# Atom_Multiout_Addon_Comp-9p.net
KiCad netlist of a schematic drawn in EAGLE
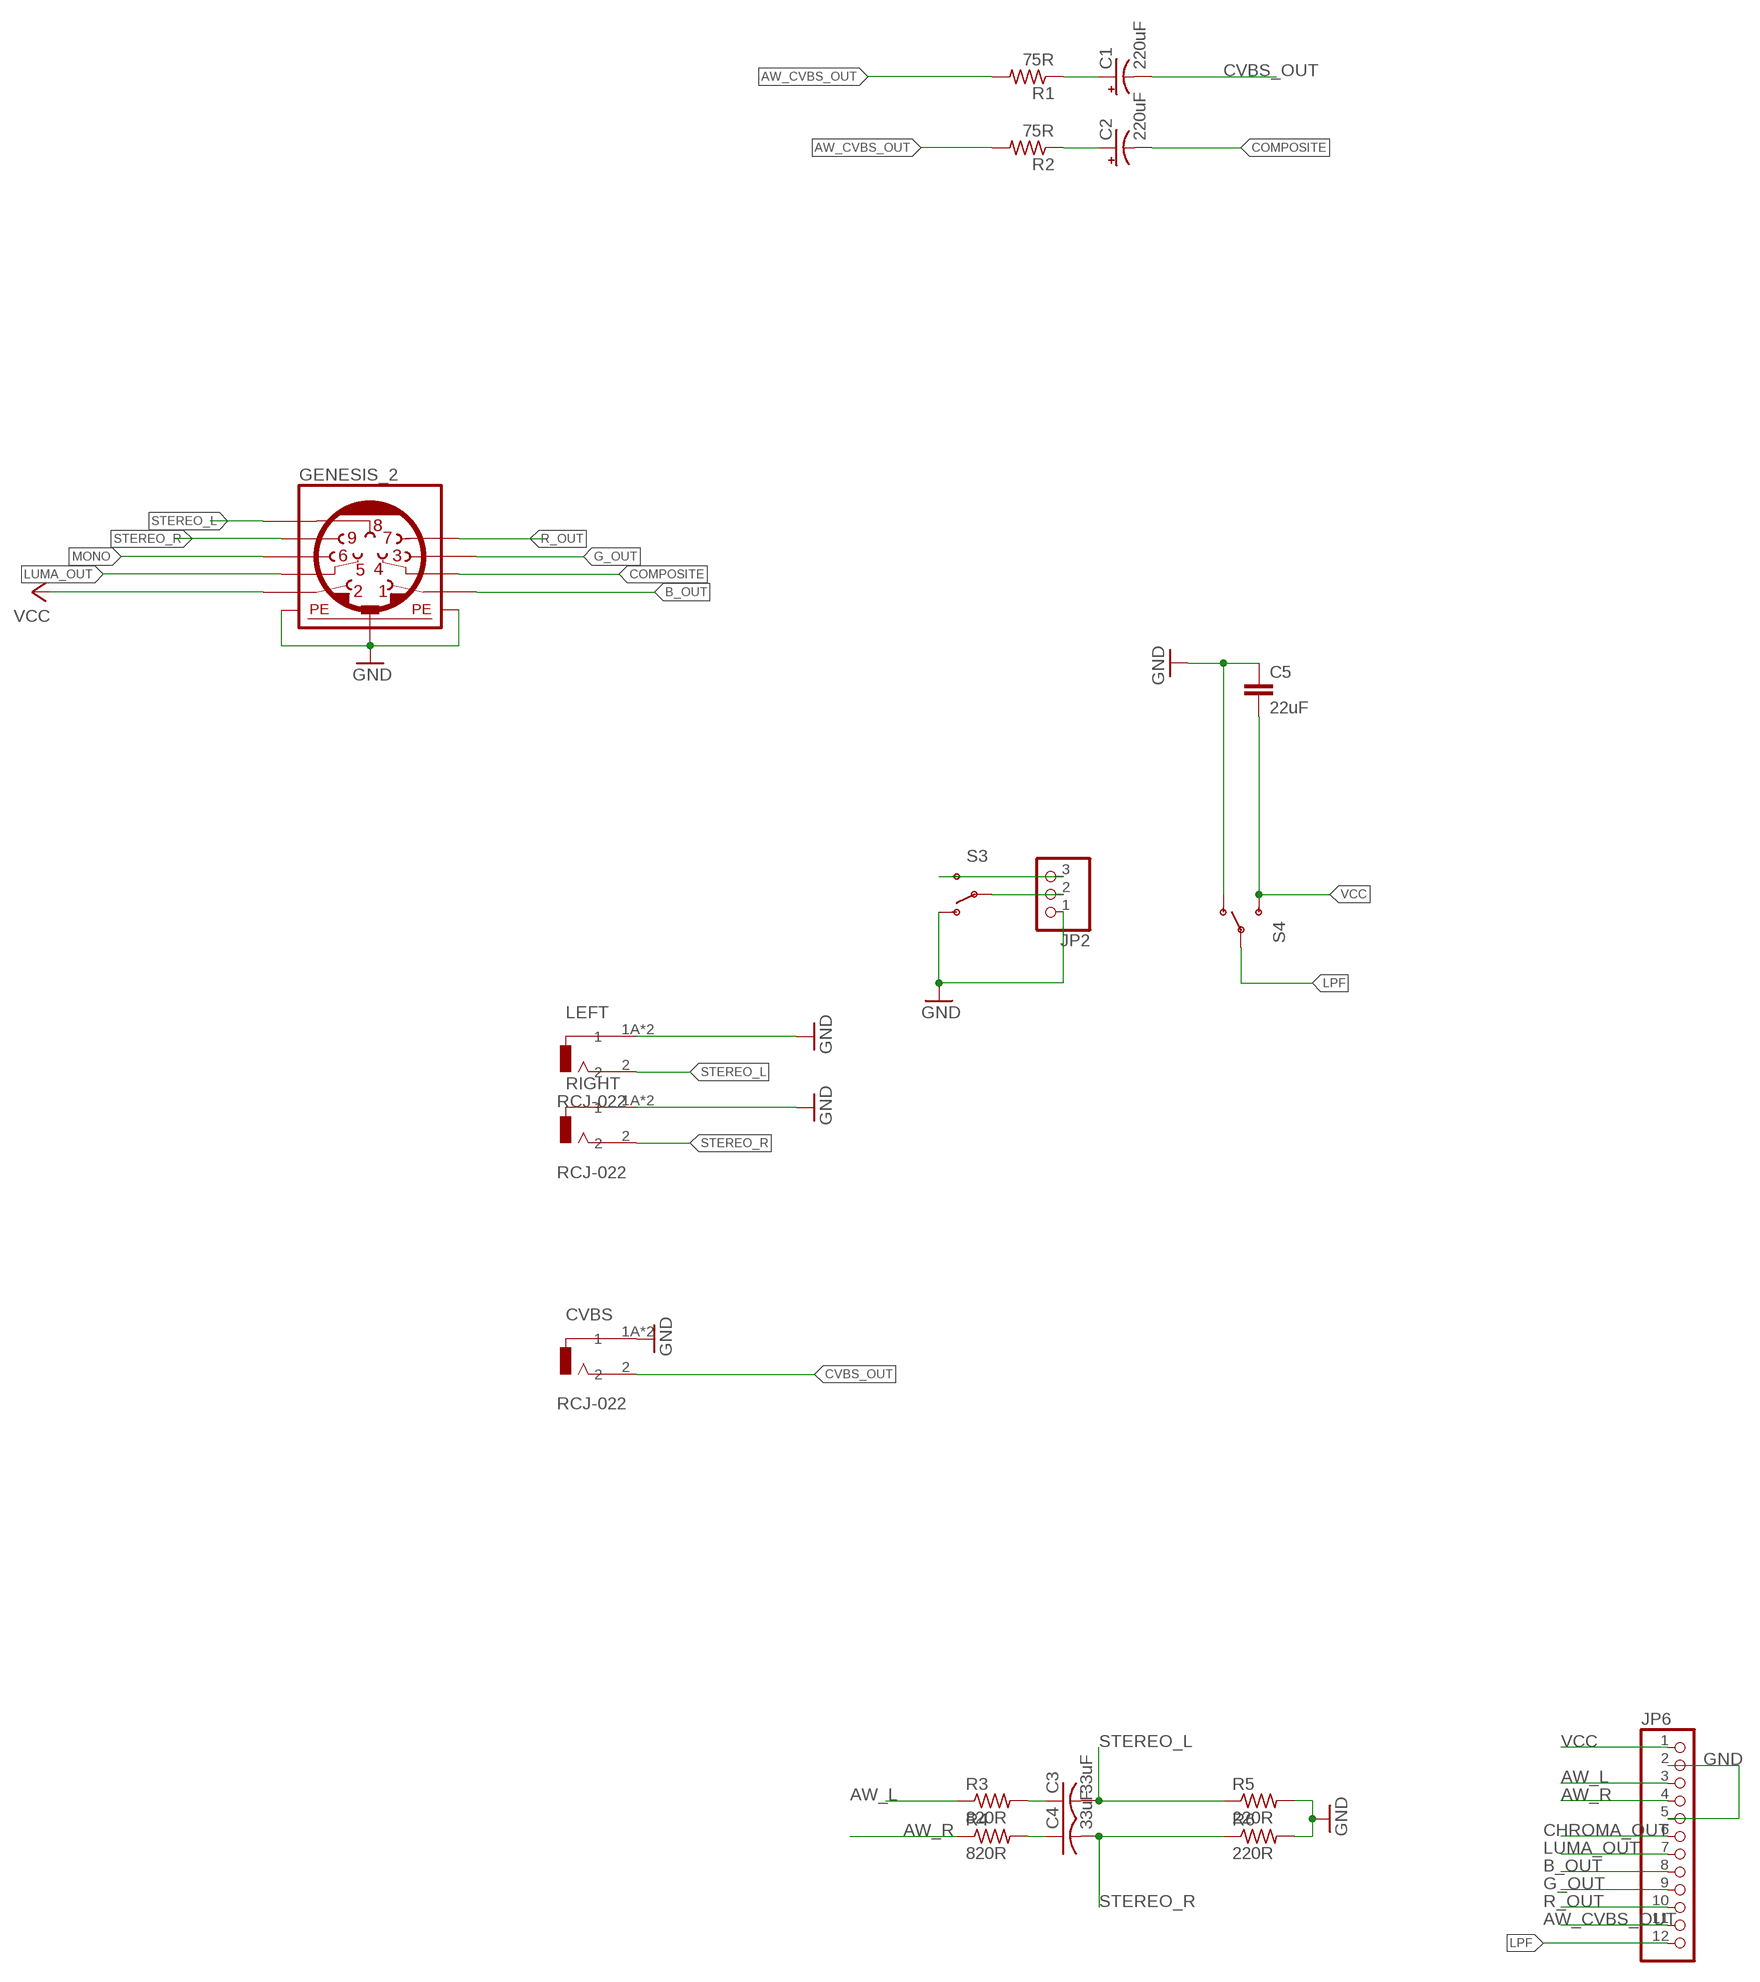
[diagram p0: schematic, sheet 1]

(export (version "E")
  (design (tool "Eeschema 10.0.6"))
  (components
    (comp (ref "C1")
      (value "220uF")
      (footprint "eagle-import:D_7343-31W")
      (libsource (lib "eagle-import") (part "CPOL-USD/7343-31W"))
    )
    (comp (ref "C2")
      (value "220uF")
      (footprint "eagle-import:D_7343-31W")
      (libsource (lib "eagle-import") (part "CPOL-USD/7343-31W"))
    )
    (comp (ref "C3")
      (value "33uF")
      (footprint "eagle-import:C1206K")
      (libsource (lib "eagle-import") (part "C-USC1206K"))
    )
    (comp (ref "C4")
      (value "33uF")
      (footprint "eagle-import:C1206K")
      (libsource (lib "eagle-import") (part "C-USC1206K"))
    )
    (comp (ref "C5")
      (value "22uF")
      (footprint "eagle-import:C0603")
      (libsource (lib "eagle-import") (part "C-EUC0603"))
    )
    (comp (ref "CVBS")
      (value "RCJ-022")
      (footprint "eagle-import:CUI_RCJ-022")
      (fields (field (name "MF") "CUI Devices"))
      (libsource (lib "eagle-import") (part "RCJ-022"))
    )
    (comp (ref "GENESIS_2")
      (value "MINI_DIN_9")
      (footprint "eagle-import:M_DIN9")
      (libsource (lib "eagle-import") (part "MINI_DIN_9"))
    )
    (comp (ref "JP2")
      (value "PINHD-1X03_2.54-S")
      (footprint "eagle-import:1X03-S")
      (libsource (lib "eagle-import") (part "PINHD-1X03_2.54-S"))
    )
    (comp (ref "JP6")
      (value "PINHD-1X12_2.54-S")
      (footprint "eagle-import:1X12-S")
      (libsource (lib "eagle-import") (part "PINHD-1X12_2.54-S"))
    )
    (comp (ref "LEFT")
      (value "RCJ-022")
      (footprint "eagle-import:CUI_RCJ-022")
      (fields (field (name "MF") "CUI Devices"))
      (libsource (lib "eagle-import") (part "RCJ-022"))
    )
    (comp (ref "R1")
      (value "75R")
      (footprint "eagle-import:R1206")
      (libsource (lib "eagle-import") (part "resistor_348_R-US_R1206"))
    )
    (comp (ref "R2")
      (value "75R")
      (footprint "eagle-import:R1206")
      (libsource (lib "eagle-import") (part "R-US_R1206"))
    )
    (comp (ref "R3")
      (value "820R")
      (footprint "eagle-import:R1206")
      (libsource (lib "eagle-import") (part "resistor_348_R-US_R1206"))
    )
    (comp (ref "R4")
      (value "820R")
      (footprint "eagle-import:R1206")
      (libsource (lib "eagle-import") (part "resistor_348_R-US_R1206"))
    )
    (comp (ref "R5")
      (value "220R")
      (footprint "eagle-import:R1206")
      (libsource (lib "eagle-import") (part "resistor_348_R-US_R1206"))
    )
    (comp (ref "R6")
      (value "220R")
      (footprint "eagle-import:R1206")
      (libsource (lib "eagle-import") (part "resistor_348_R-US_R1206"))
    )
    (comp (ref "RIGHT")
      (value "RCJ-022")
      (footprint "eagle-import:CUI_RCJ-022")
      (fields (field (name "MF") "CUI Devices"))
      (libsource (lib "eagle-import") (part "RCJ-022"))
    )
    (comp (ref "S3")
      (value "SWITCH-SPDT-SMD-A")
      (footprint "eagle-import:SWITCH-SPST-SMD-A")
      (libsource (lib "eagle-import") (part "SWITCH-SPDT-SMD-A"))
    )
    (comp (ref "S4")
      (value "SWITCH-SPDT-SMD-A")
      (footprint "eagle-import:SWITCH-SPST-SMD-A")
      (libsource (lib "eagle-import") (part "SWITCH-SPDT-SMD-A"))
    )
  )
  (nets
    (net (code "1") (name "/AW_L") (class "Default")
      (node (ref "JP6") (pin "3") (pinfunction "3_3") (pintype "passive"))
      (node (ref "R3") (pin "1") (pinfunction "1_1") (pintype "passive"))
    )
    (net (code "2") (name "/AW_R") (class "Default")
      (node (ref "JP6") (pin "4") (pinfunction "4_4") (pintype "passive"))
      (node (ref "R4") (pin "1") (pinfunction "1_1") (pintype "passive"))
    )
    (net (code "3") (name "/CHROMA_OUT") (class "Default")
      (node (ref "JP6") (pin "6") (pinfunction "6_6") (pintype "passive"))
    )
    (net (code "4") (name "AW_CVBS_OUT") (class "Default")
      (node (ref "JP6") (pin "11") (pinfunction "11_11") (pintype "passive"))
      (node (ref "R1") (pin "2") (pinfunction "2_2") (pintype "passive"))
      (node (ref "R2") (pin "2") (pinfunction "2_2") (pintype "passive"))
    )
    (net (code "5") (name "B_OUT") (class "Default")
      (node (ref "GENESIS_2") (pin "1") (pinfunction "1_1") (pintype "passive"))
      (node (ref "JP6") (pin "8") (pinfunction "8_8") (pintype "passive"))
    )
    (net (code "6") (name "COMPOSITE") (class "Default")
      (node (ref "C2") (pin "-") (pinfunction "-_-") (pintype "passive"))
      (node (ref "GENESIS_2") (pin "4") (pinfunction "4_4") (pintype "passive"))
    )
    (net (code "7") (name "CVBS_OUT") (class "Default")
      (node (ref "C1") (pin "-") (pinfunction "-_-") (pintype "passive"))
      (node (ref "CVBS") (pin "2") (pinfunction "2_2") (pintype "passive"))
    )
    (net (code "8") (name "GND") (class "Default")
      (node (ref "C5") (pin "1") (pinfunction "1_1") (pintype "passive"))
      (node (ref "CVBS") (pin "1A") (pinfunction "1_1A") (pintype "passive"))
      (node (ref "CVBS") (pin "1B") (pinfunction "1_1B") (pintype "passive"))
      (node (ref "GENESIS_2") (pin "SH1") (pinfunction "PE1_SH1") (pintype "power_in"))
      (node (ref "GENESIS_2") (pin "SH2") (pinfunction "PE2_SH2") (pintype "power_in"))
      (node (ref "GENESIS_2") (pin "SH3") (pinfunction "PE3_SH3") (pintype "power_in"))
      (node (ref "JP2") (pin "1") (pinfunction "1_1") (pintype "passive"))
      (node (ref "JP6") (pin "2") (pinfunction "2_2") (pintype "passive"))
      (node (ref "JP6") (pin "5") (pinfunction "5_5") (pintype "passive"))
      (node (ref "LEFT") (pin "1A") (pinfunction "1_1A") (pintype "passive"))
      (node (ref "LEFT") (pin "1B") (pinfunction "1_1B") (pintype "passive"))
      (node (ref "R5") (pin "2") (pinfunction "2_2") (pintype "passive"))
      (node (ref "R6") (pin "2") (pinfunction "2_2") (pintype "passive"))
      (node (ref "RIGHT") (pin "1A") (pinfunction "1_1A") (pintype "passive"))
      (node (ref "RIGHT") (pin "1B") (pinfunction "1_1B") (pintype "passive"))
      (node (ref "S3") (pin "1") (pinfunction "O_1") (pintype "passive"))
      (node (ref "S4") (pin "1") (pinfunction "O_1") (pintype "passive"))
    )
    (net (code "9") (name "G_OUT") (class "Default")
      (node (ref "GENESIS_2") (pin "3") (pinfunction "3_3") (pintype "passive"))
      (node (ref "JP6") (pin "9") (pinfunction "9_9") (pintype "passive"))
    )
    (net (code "10") (name "LPF") (class "Default")
      (node (ref "JP6") (pin "12") (pinfunction "12_12") (pintype "passive"))
      (node (ref "S4") (pin "2") (pinfunction "P_2") (pintype "passive"))
    )
    (net (code "11") (name "LUMA_OUT") (class "Default")
      (node (ref "GENESIS_2") (pin "5") (pinfunction "5_5") (pintype "passive"))
      (node (ref "JP6") (pin "7") (pinfunction "7_7") (pintype "passive"))
    )
    (net (code "12") (name "MONO") (class "Default")
      (node (ref "GENESIS_2") (pin "6") (pinfunction "6_6") (pintype "passive"))
    )
    (net (code "13") (name "Net-(C1-Pad+)") (class "Default")
      (node (ref "C1") (pin "+") (pinfunction "+_+") (pintype "passive"))
      (node (ref "R1") (pin "1") (pinfunction "1_1") (pintype "passive"))
    )
    (net (code "14") (name "Net-(C2-Pad+)") (class "Default")
      (node (ref "C2") (pin "+") (pinfunction "+_+") (pintype "passive"))
      (node (ref "R2") (pin "1") (pinfunction "1_1") (pintype "passive"))
    )
    (net (code "15") (name "Net-(C3-Pad1)") (class "Default")
      (node (ref "C3") (pin "1") (pinfunction "1_1") (pintype "passive"))
      (node (ref "R3") (pin "2") (pinfunction "2_2") (pintype "passive"))
    )
    (net (code "16") (name "Net-(C4-Pad1)") (class "Default")
      (node (ref "C4") (pin "1") (pinfunction "1_1") (pintype "passive"))
      (node (ref "R4") (pin "2") (pinfunction "2_2") (pintype "passive"))
    )
    (net (code "17") (name "Net-(S3-P)") (class "Default")
      (node (ref "JP2") (pin "2") (pinfunction "2_2") (pintype "passive"))
      (node (ref "S3") (pin "2") (pinfunction "P_2") (pintype "passive"))
    )
    (net (code "18") (name "Net-(S3-S)") (class "Default")
      (node (ref "JP2") (pin "3") (pinfunction "3_3") (pintype "passive"))
      (node (ref "S3") (pin "3") (pinfunction "S_3") (pintype "passive"))
    )
    (net (code "19") (name "R_OUT") (class "Default")
      (node (ref "GENESIS_2") (pin "7") (pinfunction "7_7") (pintype "passive"))
      (node (ref "JP6") (pin "10") (pinfunction "10_10") (pintype "passive"))
    )
    (net (code "20") (name "STEREO_L") (class "Default")
      (node (ref "C3") (pin "2") (pinfunction "2_2") (pintype "passive"))
      (node (ref "GENESIS_2") (pin "8") (pinfunction "8_8") (pintype "passive"))
      (node (ref "LEFT") (pin "2") (pinfunction "2_2") (pintype "passive"))
      (node (ref "R5") (pin "1") (pinfunction "1_1") (pintype "passive"))
    )
    (net (code "21") (name "STEREO_R") (class "Default")
      (node (ref "C4") (pin "2") (pinfunction "2_2") (pintype "passive"))
      (node (ref "GENESIS_2") (pin "9") (pinfunction "9_9") (pintype "passive"))
      (node (ref "R6") (pin "1") (pinfunction "1_1") (pintype "passive"))
      (node (ref "RIGHT") (pin "2") (pinfunction "2_2") (pintype "passive"))
    )
    (net (code "22") (name "VCC") (class "Default")
      (node (ref "C5") (pin "2") (pinfunction "2_2") (pintype "passive"))
      (node (ref "GENESIS_2") (pin "2") (pinfunction "2_2") (pintype "passive"))
      (node (ref "JP6") (pin "1") (pinfunction "1_1") (pintype "passive"))
      (node (ref "S4") (pin "3") (pinfunction "S_3") (pintype "passive"))
    )
  )
)
